# DAU_Kupplung_1_phasig_V1_8.net
KiCad netlist of a schematic drawn in EAGLE
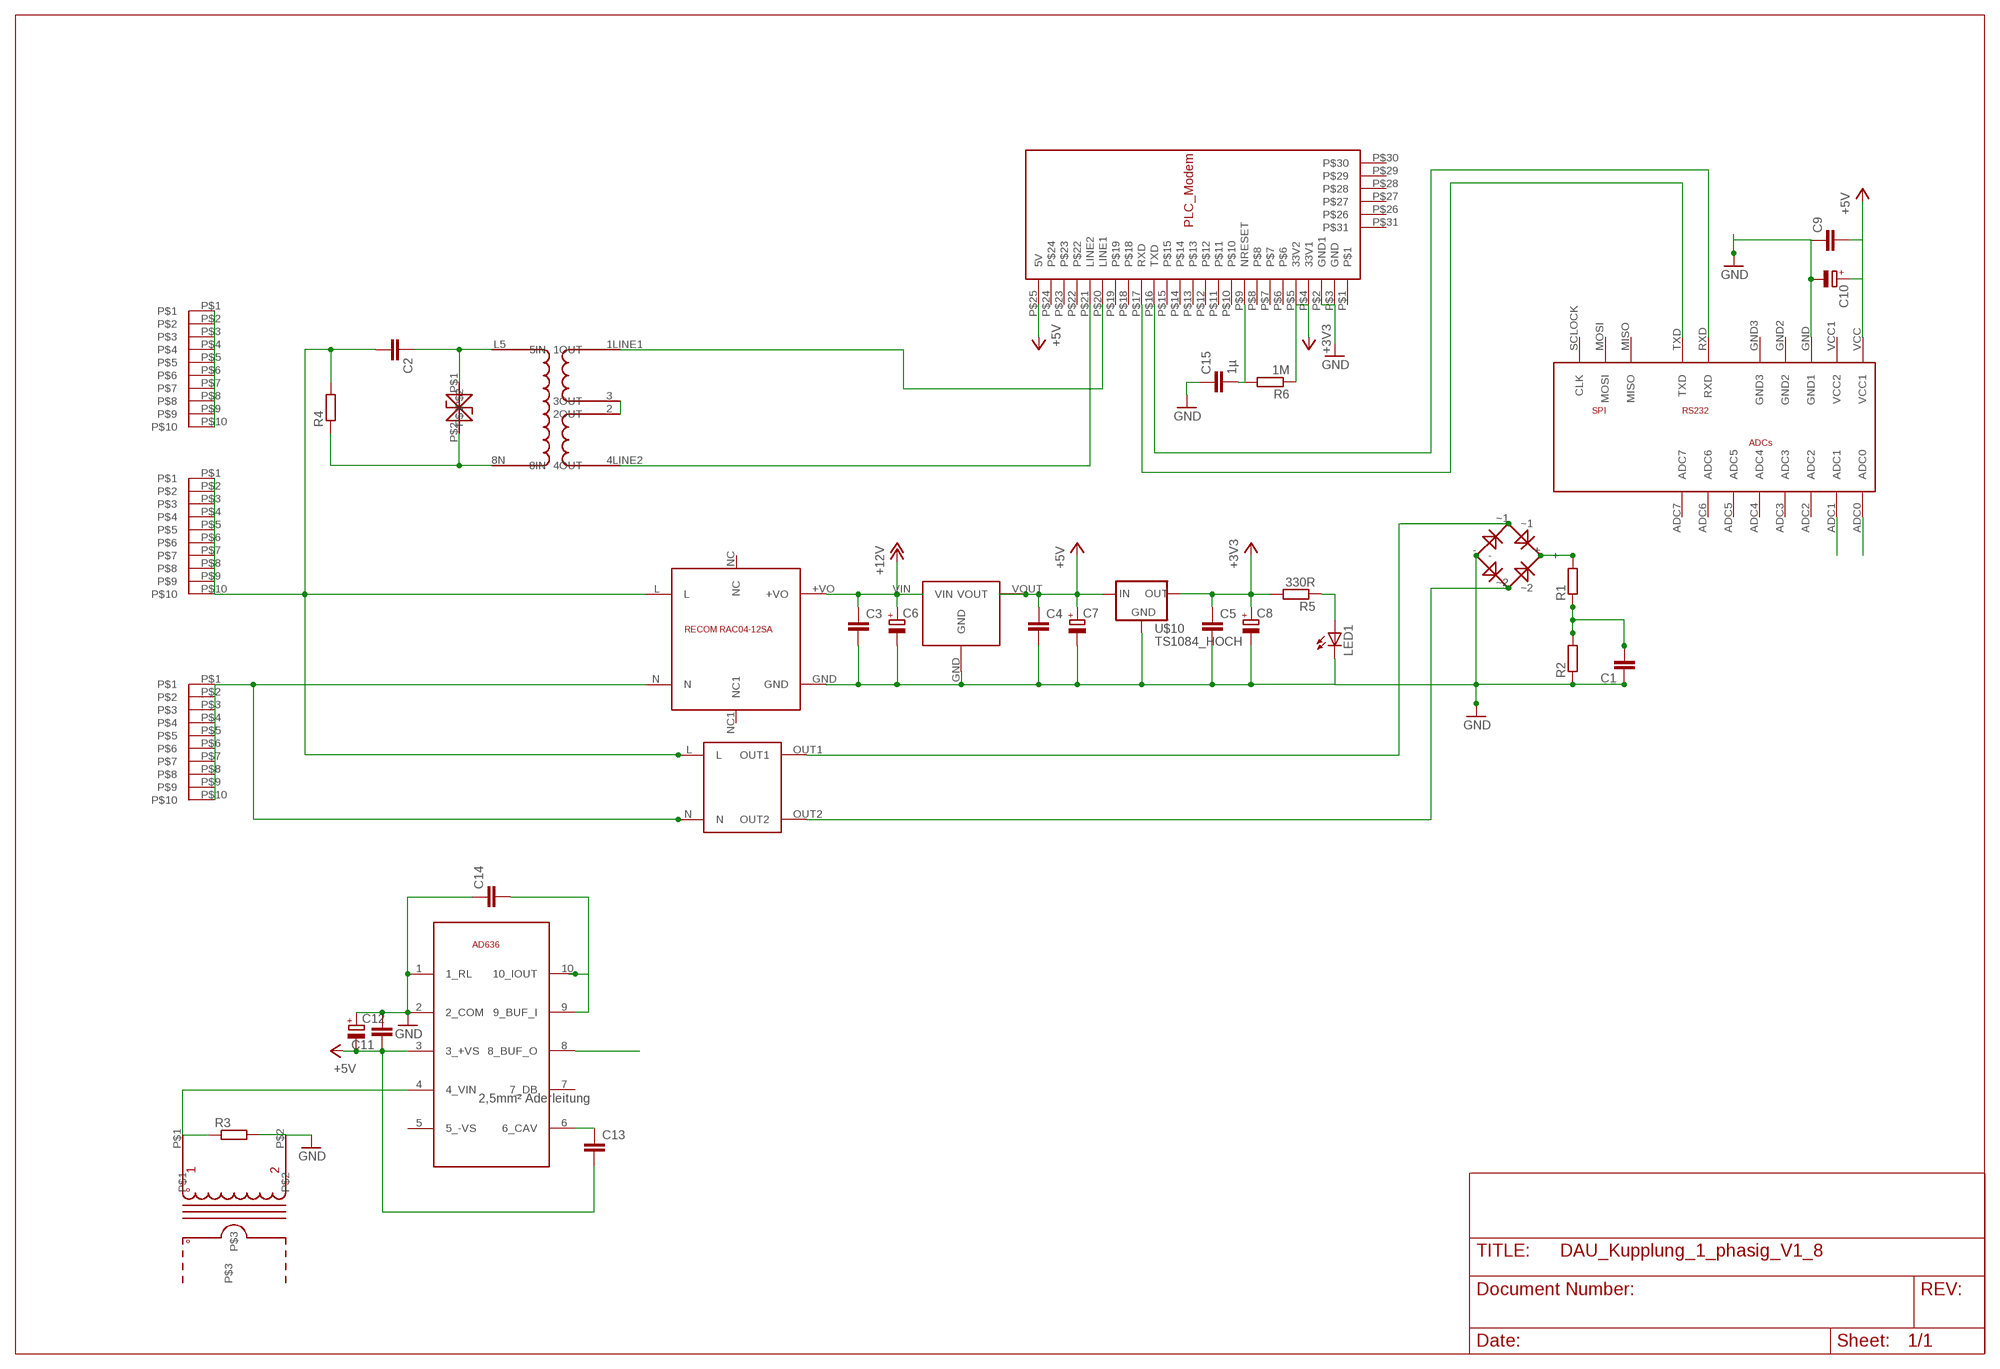
[diagram p0: schematic, sheet 1]

(export (version "E")
  (design (tool "Eeschema 10.0.6"))
  (components
    (comp (ref "C1")
      (value "C2,5-3")
      (footprint "eagle-import:C2.5-3")
      (libsource (lib "eagle-import") (part "C2,5-3"))
    )
    (comp (ref "C2")
      (value "C-EU225-087X268")
      (footprint "eagle-import:C225-087X268")
      (libsource (lib "eagle-import") (part "resistor_C-EU225-087X268"))
    )
    (comp (ref "C3")
      (value "C-EU025-040X050")
      (footprint "eagle-import:C025-040X050")
      (libsource (lib "eagle-import") (part "resistor_C-EU025-040X050"))
    )
    (comp (ref "C4")
      (value "C-EU025-040X050")
      (footprint "eagle-import:C025-040X050")
      (libsource (lib "eagle-import") (part "resistor_C-EU025-040X050"))
    )
    (comp (ref "C5")
      (value "C-EU025-040X050")
      (footprint "eagle-import:C025-040X050")
      (libsource (lib "eagle-import") (part "resistor_C-EU025-040X050"))
    )
    (comp (ref "C6")
      (value "CPOL-EUE2.5-6")
      (footprint "eagle-import:E2,5-6")
      (libsource (lib "eagle-import") (part "resistor_CPOL-EUE2.5-6"))
    )
    (comp (ref "C7")
      (value "CPOL-EUE2.5-6")
      (footprint "eagle-import:E2,5-6")
      (libsource (lib "eagle-import") (part "resistor_CPOL-EUE2.5-6"))
    )
    (comp (ref "C8")
      (value "CPOL-EUE2.5-6")
      (footprint "eagle-import:E2,5-6")
      (libsource (lib "eagle-import") (part "resistor_CPOL-EUE2.5-6"))
    )
    (comp (ref "C9")
      (value "C-EU025-040X050")
      (footprint "eagle-import:C025-040X050")
      (libsource (lib "eagle-import") (part "C-EU025-040X050"))
    )
    (comp (ref "C10")
      (value "CPOL-EUE2,5-6E")
      (footprint "eagle-import:E2,5-6E")
      (libsource (lib "eagle-import") (part "CPOL-EUE2,5-6E"))
    )
    (comp (ref "C11")
      (value "C-EU025-040X050")
      (footprint "eagle-import:C025-040X050")
      (libsource (lib "eagle-import") (part "C-EU025-040X050"))
    )
    (comp (ref "C12")
      (value "CPOL-EUE2,5-6E")
      (footprint "eagle-import:E2,5-6E")
      (libsource (lib "eagle-import") (part "CPOL-EUE2,5-6E"))
    )
    (comp (ref "C13")
      (value "C-EU025-040X050")
      (footprint "eagle-import:C025-040X050")
      (libsource (lib "eagle-import") (part "C-EU025-040X050"))
    )
    (comp (ref "C14")
      (value "C-EU025-040X050")
      (footprint "eagle-import:C025-040X050")
      (libsource (lib "eagle-import") (part "C-EU025-040X050"))
    )
    (comp (ref "C15")
      (value "1µ")
      (footprint "eagle-import:C025-040X050")
      (libsource (lib "eagle-import") (part "resistor_C-EU025-040X050"))
    )
    (comp (ref "L")
      (value "PRINT_CONNECTOR")
      (footprint "eagle-import:FASTON_DOUBLE")
      (libsource (lib "eagle-import") (part "PRINT_CONNECTOR"))
    )
    (comp (ref "LED1")
      (value "LEDSQR2X5")
      (footprint "eagle-import:LED2X5")
      (libsource (lib "eagle-import") (part "LEDSQR2X5"))
    )
    (comp (ref "N")
      (value "PRINT_CONNECTOR")
      (footprint "eagle-import:FASTON_DOUBLE")
      (libsource (lib "eagle-import") (part "PRINT_CONNECTOR"))
    )
    (comp (ref "PE")
      (value "PRINT_CONNECTOR")
      (footprint "eagle-import:FASTON_DOUBLE")
      (libsource (lib "eagle-import") (part "PRINT_CONNECTOR"))
    )
    (comp (ref "R1")
      (value "R-EU_0204/7")
      (footprint "eagle-import:0204_7")
      (libsource (lib "eagle-import") (part "R-EU_0204/7"))
    )
    (comp (ref "R2")
      (value "R-EU_0204/7")
      (footprint "eagle-import:0204_7")
      (libsource (lib "eagle-import") (part "R-EU_0204/7"))
    )
    (comp (ref "R3")
      (value "R-EU_0204/7")
      (footprint "eagle-import:0204_7")
      (libsource (lib "eagle-import") (part "R-EU_0204/7"))
    )
    (comp (ref "R4")
      (value "R-EU_0204/7")
      (footprint "eagle-import:0204_7")
      (libsource (lib "eagle-import") (part "R-EU_0204/7"))
    )
    (comp (ref "R5")
      (value "330R")
      (footprint "eagle-import:0204_7")
      (libsource (lib "eagle-import") (part "R-EU_0204/7"))
    )
    (comp (ref "R6")
      (value "1M")
      (footprint "eagle-import:0204_7")
      (libsource (lib "eagle-import") (part "R-EU_0204/7"))
    )
    (comp (ref "U$1")
      (value "RECOM_RAC04_12SA")
      (footprint "eagle-import:RAC04_12SA")
      (libsource (lib "eagle-import") (part "RECOM_RAC04_12SA"))
    )
    (comp (ref "U$2")
      (value "SICHERHEITSTRAFO")
      (footprint "eagle-import:TRAFO_0,35VA")
      (libsource (lib "eagle-import") (part "SICHERHEITSTRAFO"))
    )
    (comp (ref "U$3")
      (value "ADUC831_MINIMUM")
      (footprint "eagle-import:ADUC_MINIMUM")
      (libsource (lib "eagle-import") (part "ADUC831_MINIMUM"))
    )
    (comp (ref "U$4")
      (value "MODEMSTECKER")
      (footprint "eagle-import:MODEM_FUSS")
      (libsource (lib "eagle-import") (part "MODEMSTECKER"))
    )
    (comp (ref "U$5")
      (value "PLC_UEBERTRAGER_V2")
      (footprint "eagle-import:PLC-UEBERTRAGER_V2")
      (libsource (lib "eagle-import") (part "PLC_UEBERTRAGER_V2"))
    )
    (comp (ref "U$6")
      (value "AC1010")
      (footprint "eagle-import:AC1010")
      (libsource (lib "eagle-import") (part "AC1010"))
    )
    (comp (ref "U$7")
      (value "AD636")
      (footprint "eagle-import:TO100_10PIN")
      (libsource (lib "eagle-import") (part "AD636"))
    )
    (comp (ref "U$8")
      (value "RECTIFIER")
      (footprint "eagle-import:RECTIFIER")
      (libsource (lib "eagle-import") (part "RECTIFIER"))
    )
    (comp (ref "U$9")
      (value "SUPPRESSORDIODE15MM")
      (footprint "eagle-import:DIODE15_5MM")
      (libsource (lib "eagle-import") (part "SUPPRESSORDIODE15MM"))
    )
    (comp (ref "U$10")
      (value "TS1084_HOCH")
      (footprint "eagle-import:TS1084_HOCH")
      (libsource (lib "eagle-import") (part "TS1084_HOCH"))
    )
    (comp (ref "U$12")
      (value "RECOM_785_05")
      (footprint "eagle-import:RECOM785X")
      (libsource (lib "eagle-import") (part "RECOM_785_05"))
    )
  )
  (nets
    (net (code "1") (name "+3V3") (class "Default")
      (node (ref "C5") (pin "1") (pinfunction "1_1") (pintype "passive"))
      (node (ref "C8") (pin "+") (pinfunction "+_+") (pintype "passive"))
      (node (ref "R5") (pin "2") (pinfunction "2_2") (pintype "passive"))
      (node (ref "R6") (pin "1") (pinfunction "1_1") (pintype "passive"))
      (node (ref "U$10") (pin "OUT") (pinfunction "OUT_OUT") (pintype "passive"))
      (node (ref "U$4") (pin "P$4") (pinfunction "33V1_P$4") (pintype "bidirectional"))
      (node (ref "U$4") (pin "P$5") (pinfunction "33V2_P$5") (pintype "bidirectional"))
    )
    (net (code "2") (name "+5V") (class "Default")
      (node (ref "C10") (pin "+") (pinfunction "+_+") (pintype "passive"))
      (node (ref "C11") (pin "1") (pinfunction "1_1") (pintype "passive"))
      (node (ref "C12") (pin "-") (pinfunction "-_-") (pintype "passive"))
      (node (ref "C13") (pin "2") (pinfunction "2_2") (pintype "passive"))
      (node (ref "C4") (pin "1") (pinfunction "1_1") (pintype "passive"))
      (node (ref "C7") (pin "+") (pinfunction "+_+") (pintype "passive"))
      (node (ref "C9") (pin "2") (pinfunction "2_2") (pintype "passive"))
      (node (ref "U$10") (pin "IN") (pinfunction "IN_IN") (pintype "input"))
      (node (ref "U$12") (pin "VOUT") (pinfunction "VOUT_VOUT") (pintype "bidirectional"))
      (node (ref "U$3") (pin "VCC") (pinfunction "VCC1_VCC") (pintype "bidirectional"))
      (node (ref "U$4") (pin "P$25") (pinfunction "5V_P$25") (pintype "bidirectional"))
      (node (ref "U$7") (pin "3") (pinfunction "3_+VS_3") (pintype "input"))
    )
    (net (code "3") (name "+12V") (class "Default")
      (node (ref "C3") (pin "1") (pinfunction "1_1") (pintype "passive"))
      (node (ref "C6") (pin "+") (pinfunction "+_+") (pintype "passive"))
      (node (ref "U$1") (pin "+VO") (pinfunction "+VO_+VO") (pintype "bidirectional"))
      (node (ref "U$12") (pin "VIN") (pinfunction "VIN_VIN") (pintype "bidirectional"))
    )
    (net (code "4") (name "/ADC0") (class "Default")
      (node (ref "C1") (pin "2") (pinfunction "2_2") (pintype "passive"))
      (node (ref "R1") (pin "1") (pinfunction "1_1") (pintype "passive"))
      (node (ref "R2") (pin "2") (pinfunction "2_2") (pintype "passive"))
      (node (ref "U$3") (pin "ADC0") (pinfunction "ADC0_ADC0") (pintype "bidirectional"))
    )
    (net (code "5") (name "/ADC1") (class "Default")
      (node (ref "U$3") (pin "ADC1") (pinfunction "ADC1_ADC1") (pintype "bidirectional"))
      (node (ref "U$7") (pin "8") (pinfunction "8_BUF_O_8") (pintype "output"))
    )
    (net (code "6") (name "GND") (class "Default")
      (node (ref "C1") (pin "1") (pinfunction "1_1") (pintype "passive"))
      (node (ref "C10") (pin "-") (pinfunction "-_-") (pintype "passive"))
      (node (ref "C11") (pin "2") (pinfunction "2_2") (pintype "passive"))
      (node (ref "C12") (pin "+") (pinfunction "+_+") (pintype "passive"))
      (node (ref "C14") (pin "1") (pinfunction "1_1") (pintype "passive"))
      (node (ref "C15") (pin "1") (pinfunction "1_1") (pintype "passive"))
      (node (ref "C3") (pin "2") (pinfunction "2_2") (pintype "passive"))
      (node (ref "C4") (pin "2") (pinfunction "2_2") (pintype "passive"))
      (node (ref "C5") (pin "2") (pinfunction "2_2") (pintype "passive"))
      (node (ref "C6") (pin "-") (pinfunction "-_-") (pintype "passive"))
      (node (ref "C7") (pin "-") (pinfunction "-_-") (pintype "passive"))
      (node (ref "C8") (pin "-") (pinfunction "-_-") (pintype "passive"))
      (node (ref "C9") (pin "1") (pinfunction "1_1") (pintype "passive"))
      (node (ref "LED1") (pin "K") (pinfunction "C_K") (pintype "passive"))
      (node (ref "R2") (pin "1") (pinfunction "1_1") (pintype "passive"))
      (node (ref "R3") (pin "2") (pinfunction "2_2") (pintype "passive"))
      (node (ref "U$1") (pin "GND") (pinfunction "GND_GND") (pintype "bidirectional"))
      (node (ref "U$10") (pin "GND") (pinfunction "GND_GND") (pintype "input"))
      (node (ref "U$12") (pin "GND") (pinfunction "GND_GND") (pintype "bidirectional"))
      (node (ref "U$3") (pin "GND") (pinfunction "GND1_GND") (pintype "bidirectional"))
      (node (ref "U$4") (pin "P$2") (pinfunction "GND1_P$2") (pintype "bidirectional"))
      (node (ref "U$4") (pin "P$3") (pinfunction "GND_P$3") (pintype "bidirectional"))
      (node (ref "U$6") (pin "P$2") (pinfunction "P$2_P$2") (pintype "bidirectional"))
      (node (ref "U$7") (pin "1") (pinfunction "1_RL_1") (pintype "bidirectional"))
      (node (ref "U$7") (pin "2") (pinfunction "2_COM_2") (pintype "bidirectional"))
      (node (ref "U$8") (pin "-") (pinfunction "-_-") (pintype "bidirectional"))
    )
    (net (code "7") (name "Net-(C2-Pad2)") (class "Default")
      (node (ref "C2") (pin "2") (pinfunction "2_2") (pintype "passive"))
      (node (ref "L") (pin "P$1") (pinfunction "P$1_P$1") (pintype "bidirectional"))
      (node (ref "L") (pin "P$10") (pinfunction "P$10_P$10") (pintype "bidirectional"))
      (node (ref "L") (pin "P$2") (pinfunction "P$2_P$2") (pintype "bidirectional"))
      (node (ref "L") (pin "P$3") (pinfunction "P$3_P$3") (pintype "bidirectional"))
      (node (ref "L") (pin "P$4") (pinfunction "P$4_P$4") (pintype "bidirectional"))
      (node (ref "L") (pin "P$5") (pinfunction "P$5_P$5") (pintype "bidirectional"))
      (node (ref "L") (pin "P$6") (pinfunction "P$6_P$6") (pintype "bidirectional"))
      (node (ref "L") (pin "P$7") (pinfunction "P$7_P$7") (pintype "bidirectional"))
      (node (ref "L") (pin "P$8") (pinfunction "P$8_P$8") (pintype "bidirectional"))
      (node (ref "L") (pin "P$9") (pinfunction "P$9_P$9") (pintype "bidirectional"))
      (node (ref "R4") (pin "2") (pinfunction "2_2") (pintype "passive"))
      (node (ref "U$1") (pin "L") (pinfunction "L_L") (pintype "bidirectional"))
      (node (ref "U$2") (pin "L") (pinfunction "L_L") (pintype "bidirectional"))
    )
    (net (code "8") (name "Net-(LED1-PadA)") (class "Default")
      (node (ref "LED1") (pin "A") (pinfunction "A_A") (pintype "passive"))
      (node (ref "R5") (pin "1") (pinfunction "1_1") (pintype "passive"))
    )
    (net (code "9") (name "Net-(N-PadP$1)") (class "Default")
      (node (ref "N") (pin "P$1") (pinfunction "P$1_P$1") (pintype "bidirectional"))
      (node (ref "N") (pin "P$10") (pinfunction "P$10_P$10") (pintype "bidirectional"))
      (node (ref "N") (pin "P$2") (pinfunction "P$2_P$2") (pintype "bidirectional"))
      (node (ref "N") (pin "P$3") (pinfunction "P$3_P$3") (pintype "bidirectional"))
      (node (ref "N") (pin "P$4") (pinfunction "P$4_P$4") (pintype "bidirectional"))
      (node (ref "N") (pin "P$5") (pinfunction "P$5_P$5") (pintype "bidirectional"))
      (node (ref "N") (pin "P$6") (pinfunction "P$6_P$6") (pintype "bidirectional"))
      (node (ref "N") (pin "P$7") (pinfunction "P$7_P$7") (pintype "bidirectional"))
      (node (ref "N") (pin "P$8") (pinfunction "P$8_P$8") (pintype "bidirectional"))
      (node (ref "N") (pin "P$9") (pinfunction "P$9_P$9") (pintype "bidirectional"))
      (node (ref "U$1") (pin "N") (pinfunction "N_N") (pintype "bidirectional"))
      (node (ref "U$2") (pin "N") (pinfunction "N_N") (pintype "bidirectional"))
    )
    (net (code "10") (name "Net-(PE-PadP$1)") (class "Default")
      (node (ref "PE") (pin "P$1") (pinfunction "P$1_P$1") (pintype "bidirectional"))
      (node (ref "PE") (pin "P$10") (pinfunction "P$10_P$10") (pintype "bidirectional"))
      (node (ref "PE") (pin "P$2") (pinfunction "P$2_P$2") (pintype "bidirectional"))
      (node (ref "PE") (pin "P$3") (pinfunction "P$3_P$3") (pintype "bidirectional"))
      (node (ref "PE") (pin "P$4") (pinfunction "P$4_P$4") (pintype "bidirectional"))
      (node (ref "PE") (pin "P$5") (pinfunction "P$5_P$5") (pintype "bidirectional"))
      (node (ref "PE") (pin "P$6") (pinfunction "P$6_P$6") (pintype "bidirectional"))
      (node (ref "PE") (pin "P$7") (pinfunction "P$7_P$7") (pintype "bidirectional"))
      (node (ref "PE") (pin "P$8") (pinfunction "P$8_P$8") (pintype "bidirectional"))
      (node (ref "PE") (pin "P$9") (pinfunction "P$9_P$9") (pintype "bidirectional"))
    )
    (net (code "11") (name "Net-(R1-Pad2)") (class "Default")
      (node (ref "R1") (pin "2") (pinfunction "2_2") (pintype "passive"))
      (node (ref "U$8") (pin "+") (pinfunction "+_+") (pintype "bidirectional"))
    )
    (net (code "12") (name "Net-(U$4-LINE1)") (class "Default")
      (node (ref "U$4") (pin "P$20") (pinfunction "LINE1_P$20") (pintype "bidirectional"))
      (node (ref "U$5") (pin "1LINE1") (pinfunction "1OUT_1LINE1") (pintype "output"))
    )
    (net (code "13") (name "Net-(U$4-LINE2)") (class "Default")
      (node (ref "U$4") (pin "P$21") (pinfunction "LINE2_P$21") (pintype "bidirectional"))
      (node (ref "U$5") (pin "4LINE2") (pinfunction "4OUT_4LINE2") (pintype "output"))
    )
    (net (code "14") (name "Net-(U$4-NRESET)") (class "Default")
      (node (ref "C15") (pin "2") (pinfunction "2_2") (pintype "passive"))
      (node (ref "R6") (pin "2") (pinfunction "2_2") (pintype "passive"))
      (node (ref "U$4") (pin "P$9") (pinfunction "NRESET_P$9") (pintype "bidirectional"))
    )
    (net (code "15") (name "Net-(U$4-RXD)") (class "Default")
      (node (ref "U$3") (pin "TXD") (pinfunction "TXD_TXD") (pintype "bidirectional"))
      (node (ref "U$4") (pin "P$17") (pinfunction "RXD_P$17") (pintype "bidirectional"))
    )
    (net (code "16") (name "Net-(U$4-TXD)") (class "Default")
      (node (ref "U$3") (pin "RXD") (pinfunction "RXD_RXD") (pintype "bidirectional"))
      (node (ref "U$4") (pin "P$16") (pinfunction "TXD_P$16") (pintype "bidirectional"))
    )
    (net (code "17") (name "Net-(U$5-2OUT)") (class "Default")
      (node (ref "U$5") (pin "2") (pinfunction "2OUT_2") (pintype "output"))
      (node (ref "U$5") (pin "3") (pinfunction "3OUT_3") (pintype "output"))
    )
    (net (code "18") (name "Net-(U$5-5IN)") (class "Default")
      (node (ref "C2") (pin "1") (pinfunction "1_1") (pintype "passive"))
      (node (ref "U$5") (pin "L5") (pinfunction "5IN_L5") (pintype "input"))
      (node (ref "U$9") (pin "P$1") (pinfunction "P$1_P$1") (pintype "bidirectional"))
    )
    (net (code "19") (name "Net-(U$5-8IN)") (class "Default")
      (node (ref "R4") (pin "1") (pinfunction "1_1") (pintype "passive"))
      (node (ref "U$5") (pin "8N") (pinfunction "8IN_8N") (pintype "input"))
      (node (ref "U$9") (pin "P$2") (pinfunction "P$2_P$2") (pintype "bidirectional"))
    )
    (net (code "20") (name "Net-(U$7-4_VIN)") (class "Default")
      (node (ref "R3") (pin "1") (pinfunction "1_1") (pintype "passive"))
      (node (ref "U$6") (pin "P$1") (pinfunction "P$1_P$1") (pintype "bidirectional"))
      (node (ref "U$7") (pin "4") (pinfunction "4_VIN_4") (pintype "input"))
    )
    (net (code "21") (name "Net-(U$7-6_CAV)") (class "Default")
      (node (ref "C13") (pin "1") (pinfunction "1_1") (pintype "passive"))
      (node (ref "U$7") (pin "6") (pinfunction "6_CAV_6") (pintype "input"))
    )
    (net (code "22") (name "Net-(U$7-10_IOUT)") (class "Default")
      (node (ref "C14") (pin "2") (pinfunction "2_2") (pintype "passive"))
      (node (ref "U$7") (pin "10") (pinfunction "10_IOUT_10") (pintype "output"))
      (node (ref "U$7") (pin "9") (pinfunction "9_BUF_I_9") (pintype "input"))
    )
    (net (code "23") (name "Net-(U$8-~{1})") (class "Default")
      (node (ref "U$2") (pin "OUT1") (pinfunction "OUT1_OUT1") (pintype "bidirectional"))
      (node (ref "U$8") (pin "~1") (pinfunction "~{1}_~1") (pintype "bidirectional"))
    )
    (net (code "24") (name "Net-(U$8-~{2})") (class "Default")
      (node (ref "U$2") (pin "OUT2") (pinfunction "OUT2_OUT2") (pintype "bidirectional"))
      (node (ref "U$8") (pin "~2") (pinfunction "~{2}_~2") (pintype "bidirectional"))
    )
    (net (code "25") (name "unconnected-(U$1-PadNC)") (class "Default")
      (node (ref "U$1") (pin "NC") (pinfunction "NC_NC") (pintype "bidirectional"))
    )
    (net (code "26") (name "unconnected-(U$1-PadNC1)") (class "Default")
      (node (ref "U$1") (pin "NC1") (pinfunction "NC1_NC1") (pintype "bidirectional"))
    )
    (net (code "27") (name "unconnected-(U$3-CLK-PadSCLOCK)") (class "Default")
      (node (ref "U$3") (pin "SCLOCK") (pinfunction "CLK_SCLOCK") (pintype "bidirectional"))
    )
    (net (code "28") (name "unconnected-(U$3-PadADC2)") (class "Default")
      (node (ref "U$3") (pin "ADC2") (pinfunction "ADC2_ADC2") (pintype "bidirectional"))
    )
    (net (code "29") (name "unconnected-(U$3-PadADC3)") (class "Default")
      (node (ref "U$3") (pin "ADC3") (pinfunction "ADC3_ADC3") (pintype "bidirectional"))
    )
    (net (code "30") (name "unconnected-(U$3-PadADC4)") (class "Default")
      (node (ref "U$3") (pin "ADC4") (pinfunction "ADC4_ADC4") (pintype "bidirectional"))
    )
    (net (code "31") (name "unconnected-(U$3-PadADC5)") (class "Default")
      (node (ref "U$3") (pin "ADC5") (pinfunction "ADC5_ADC5") (pintype "bidirectional"))
    )
    (net (code "32") (name "unconnected-(U$3-PadADC6)") (class "Default")
      (node (ref "U$3") (pin "ADC6") (pinfunction "ADC6_ADC6") (pintype "bidirectional"))
    )
    (net (code "33") (name "unconnected-(U$3-PadADC7)") (class "Default")
      (node (ref "U$3") (pin "ADC7") (pinfunction "ADC7_ADC7") (pintype "bidirectional"))
    )
    (net (code "34") (name "unconnected-(U$3-PadGND2)") (class "Default")
      (node (ref "U$3") (pin "GND2") (pinfunction "GND2_GND2") (pintype "bidirectional"))
    )
    (net (code "35") (name "unconnected-(U$3-PadGND3)") (class "Default")
      (node (ref "U$3") (pin "GND3") (pinfunction "GND3_GND3") (pintype "bidirectional"))
    )
    (net (code "36") (name "unconnected-(U$3-PadMISO)") (class "Default")
      (node (ref "U$3") (pin "MISO") (pinfunction "MISO_MISO") (pintype "bidirectional"))
    )
    (net (code "37") (name "unconnected-(U$3-PadMOSI)") (class "Default")
      (node (ref "U$3") (pin "MOSI") (pinfunction "MOSI_MOSI") (pintype "bidirectional"))
    )
    (net (code "38") (name "unconnected-(U$3-VCC2-PadVCC1)") (class "Default")
      (node (ref "U$3") (pin "VCC1") (pinfunction "VCC2_VCC1") (pintype "bidirectional"))
    )
    (net (code "39") (name "unconnected-(U$4-PadP$1)") (class "Default")
      (node (ref "U$4") (pin "P$1") (pinfunction "P$1_P$1") (pintype "bidirectional"))
    )
    (net (code "40") (name "unconnected-(U$4-PadP$6)") (class "Default")
      (node (ref "U$4") (pin "P$6") (pinfunction "P$6_P$6") (pintype "bidirectional"))
    )
    (net (code "41") (name "unconnected-(U$4-PadP$7)") (class "Default")
      (node (ref "U$4") (pin "P$7") (pinfunction "P$7_P$7") (pintype "bidirectional"))
    )
    (net (code "42") (name "unconnected-(U$4-PadP$8)") (class "Default")
      (node (ref "U$4") (pin "P$8") (pinfunction "P$8_P$8") (pintype "bidirectional"))
    )
    (net (code "43") (name "unconnected-(U$4-PadP$10)") (class "Default")
      (node (ref "U$4") (pin "P$10") (pinfunction "P$10_P$10") (pintype "bidirectional"))
    )
    (net (code "44") (name "unconnected-(U$4-PadP$11)") (class "Default")
      (node (ref "U$4") (pin "P$11") (pinfunction "P$11_P$11") (pintype "bidirectional"))
    )
    (net (code "45") (name "unconnected-(U$4-PadP$12)") (class "Default")
      (node (ref "U$4") (pin "P$12") (pinfunction "P$12_P$12") (pintype "bidirectional"))
    )
    (net (code "46") (name "unconnected-(U$4-PadP$13)") (class "Default")
      (node (ref "U$4") (pin "P$13") (pinfunction "P$13_P$13") (pintype "bidirectional"))
    )
    (net (code "47") (name "unconnected-(U$4-PadP$14)") (class "Default")
      (node (ref "U$4") (pin "P$14") (pinfunction "P$14_P$14") (pintype "bidirectional"))
    )
    (net (code "48") (name "unconnected-(U$4-PadP$15)") (class "Default")
      (node (ref "U$4") (pin "P$15") (pinfunction "P$15_P$15") (pintype "bidirectional"))
    )
    (net (code "49") (name "unconnected-(U$4-PadP$18)") (class "Default")
      (node (ref "U$4") (pin "P$18") (pinfunction "P$18_P$18") (pintype "bidirectional"))
    )
    (net (code "50") (name "unconnected-(U$4-PadP$19)") (class "Default")
      (node (ref "U$4") (pin "P$19") (pinfunction "P$19_P$19") (pintype "bidirectional"))
    )
    (net (code "51") (name "unconnected-(U$4-PadP$22)") (class "Default")
      (node (ref "U$4") (pin "P$22") (pinfunction "P$22_P$22") (pintype "bidirectional"))
    )
    (net (code "52") (name "unconnected-(U$4-PadP$23)") (class "Default")
      (node (ref "U$4") (pin "P$23") (pinfunction "P$23_P$23") (pintype "bidirectional"))
    )
    (net (code "53") (name "unconnected-(U$4-PadP$24)") (class "Default")
      (node (ref "U$4") (pin "P$24") (pinfunction "P$24_P$24") (pintype "bidirectional"))
    )
    (net (code "54") (name "unconnected-(U$4-PadP$26)") (class "Default")
      (node (ref "U$4") (pin "P$26") (pinfunction "P$26_P$26") (pintype "bidirectional"))
    )
    (net (code "55") (name "unconnected-(U$4-PadP$27)") (class "Default")
      (node (ref "U$4") (pin "P$27") (pinfunction "P$27_P$27") (pintype "bidirectional"))
    )
    (net (code "56") (name "unconnected-(U$4-PadP$28)") (class "Default")
      (node (ref "U$4") (pin "P$28") (pinfunction "P$28_P$28") (pintype "bidirectional"))
    )
    (net (code "57") (name "unconnected-(U$4-PadP$29)") (class "Default")
      (node (ref "U$4") (pin "P$29") (pinfunction "P$29_P$29") (pintype "bidirectional"))
    )
    (net (code "58") (name "unconnected-(U$4-PadP$30)") (class "Default")
      (node (ref "U$4") (pin "P$30") (pinfunction "P$30_P$30") (pintype "bidirectional"))
    )
    (net (code "59") (name "unconnected-(U$4-PadP$31)") (class "Default")
      (node (ref "U$4") (pin "P$31") (pinfunction "P$31_P$31") (pintype "bidirectional"))
    )
    (net (code "60") (name "unconnected-(U$6-PadP$3)") (class "Default")
      (node (ref "U$6") (pin "P$3") (pinfunction "P$3_P$3") (pintype "bidirectional"))
    )
    (net (code "61") (name "unconnected-(U$7-5_-VS-Pad5)") (class "Default")
      (node (ref "U$7") (pin "5") (pinfunction "5_-VS_5") (pintype "input"))
    )
    (net (code "62") (name "unconnected-(U$7-7_DB-Pad7)") (class "Default")
      (node (ref "U$7") (pin "7") (pinfunction "7_DB_7") (pintype "output"))
    )
  )
)
